# 14_-_MCU.net
KiCad netlist of a schematic drawn in Altium Designer
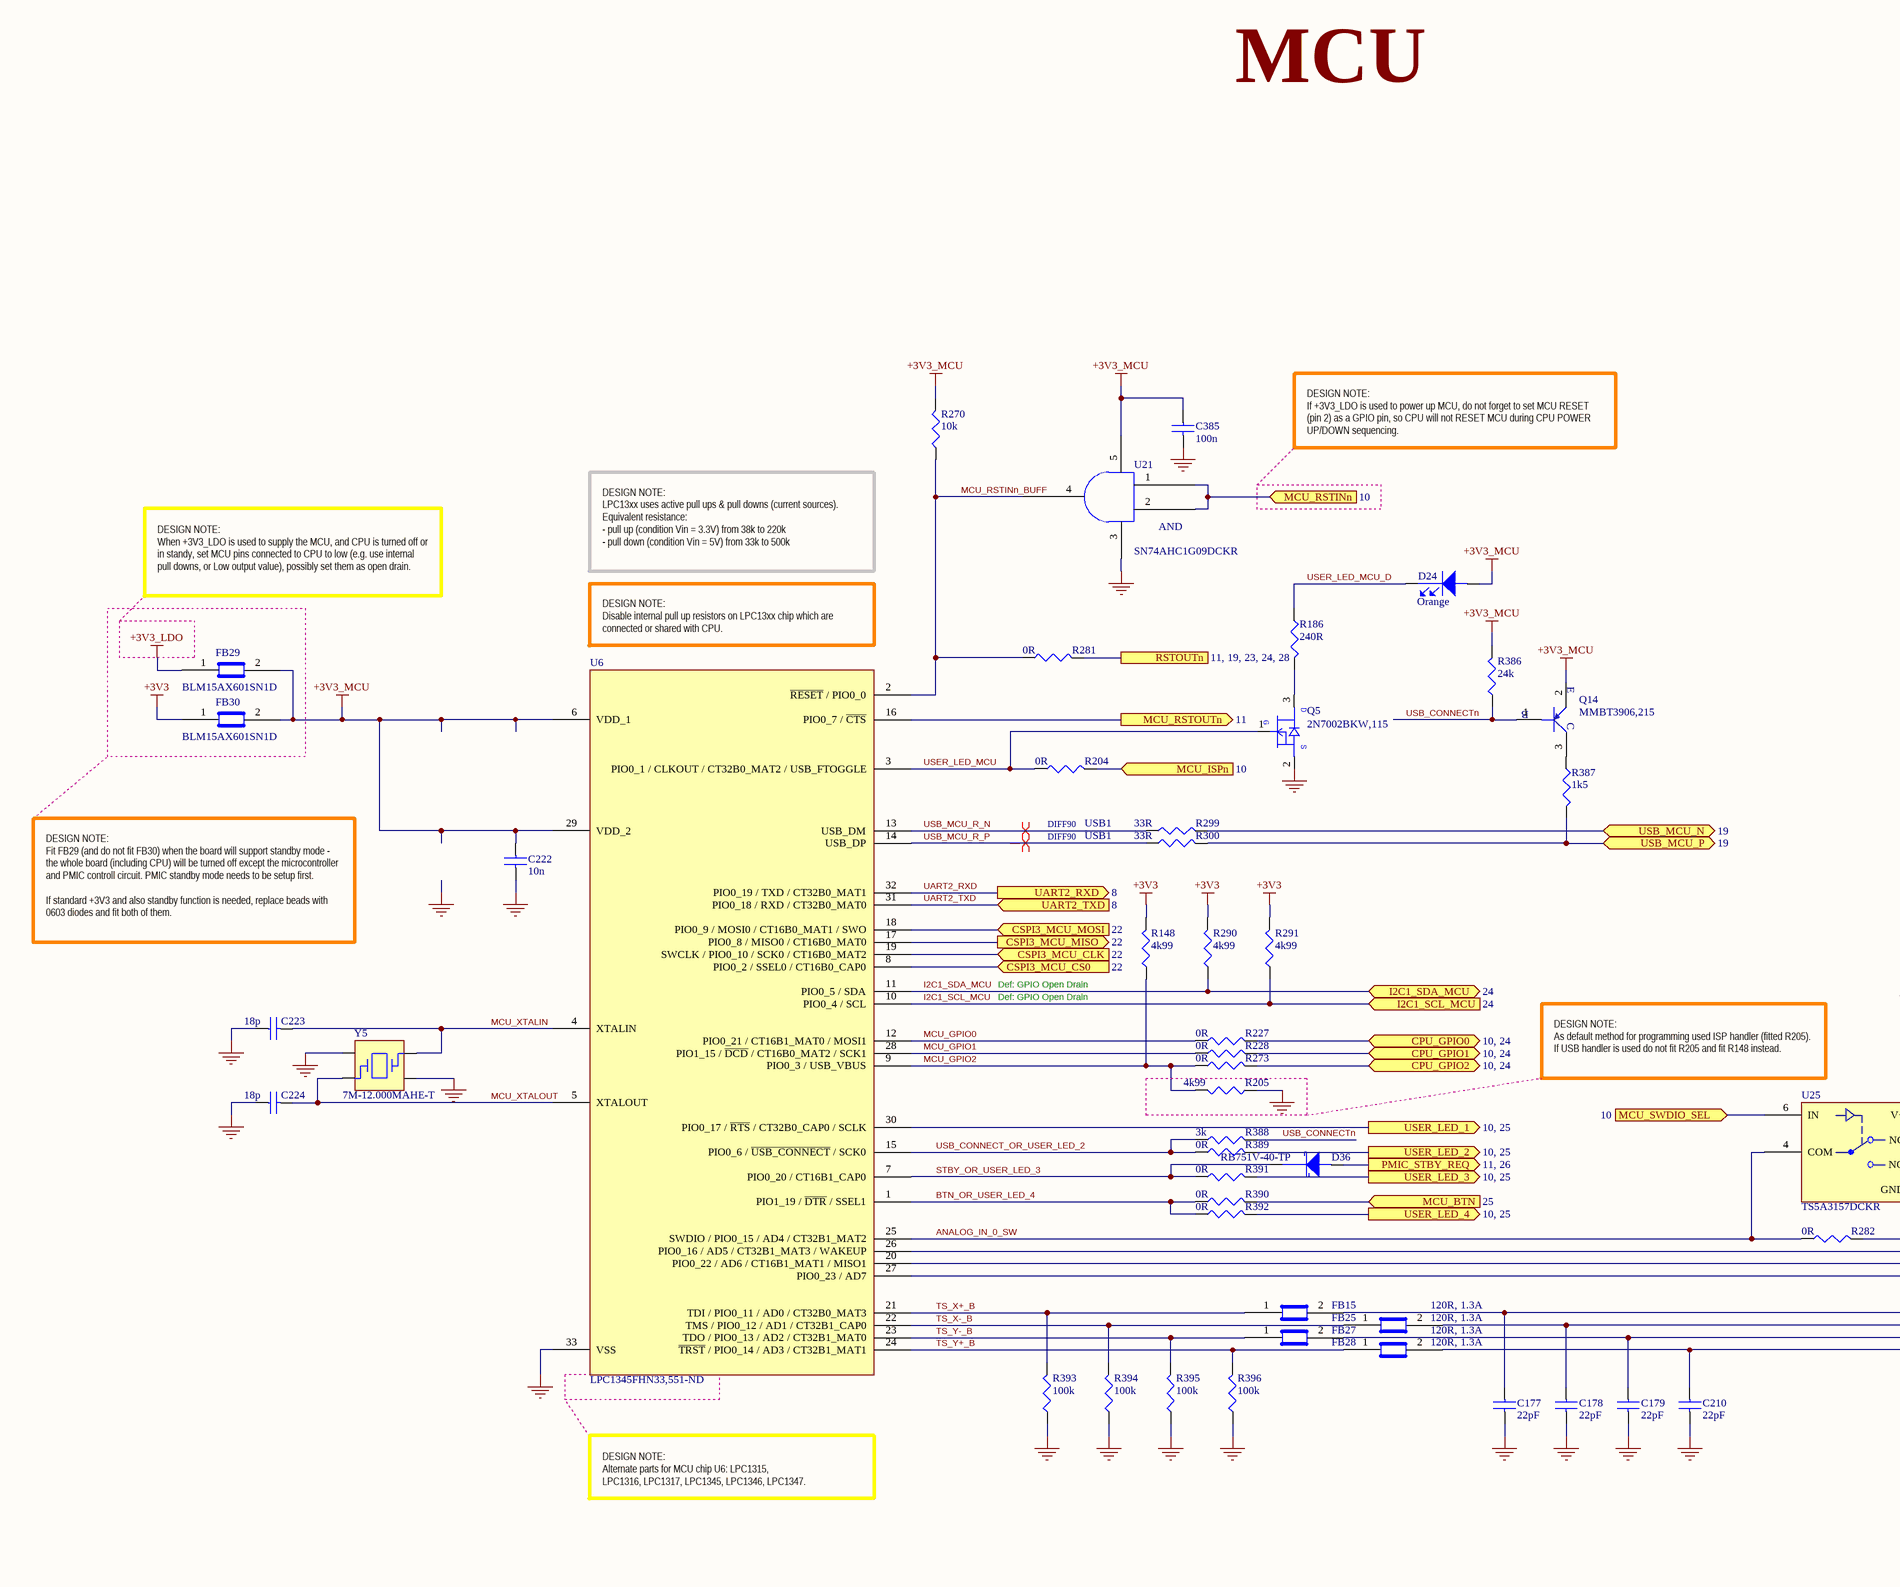
[diagram p0: [14] - MCU.SchDoc, left]
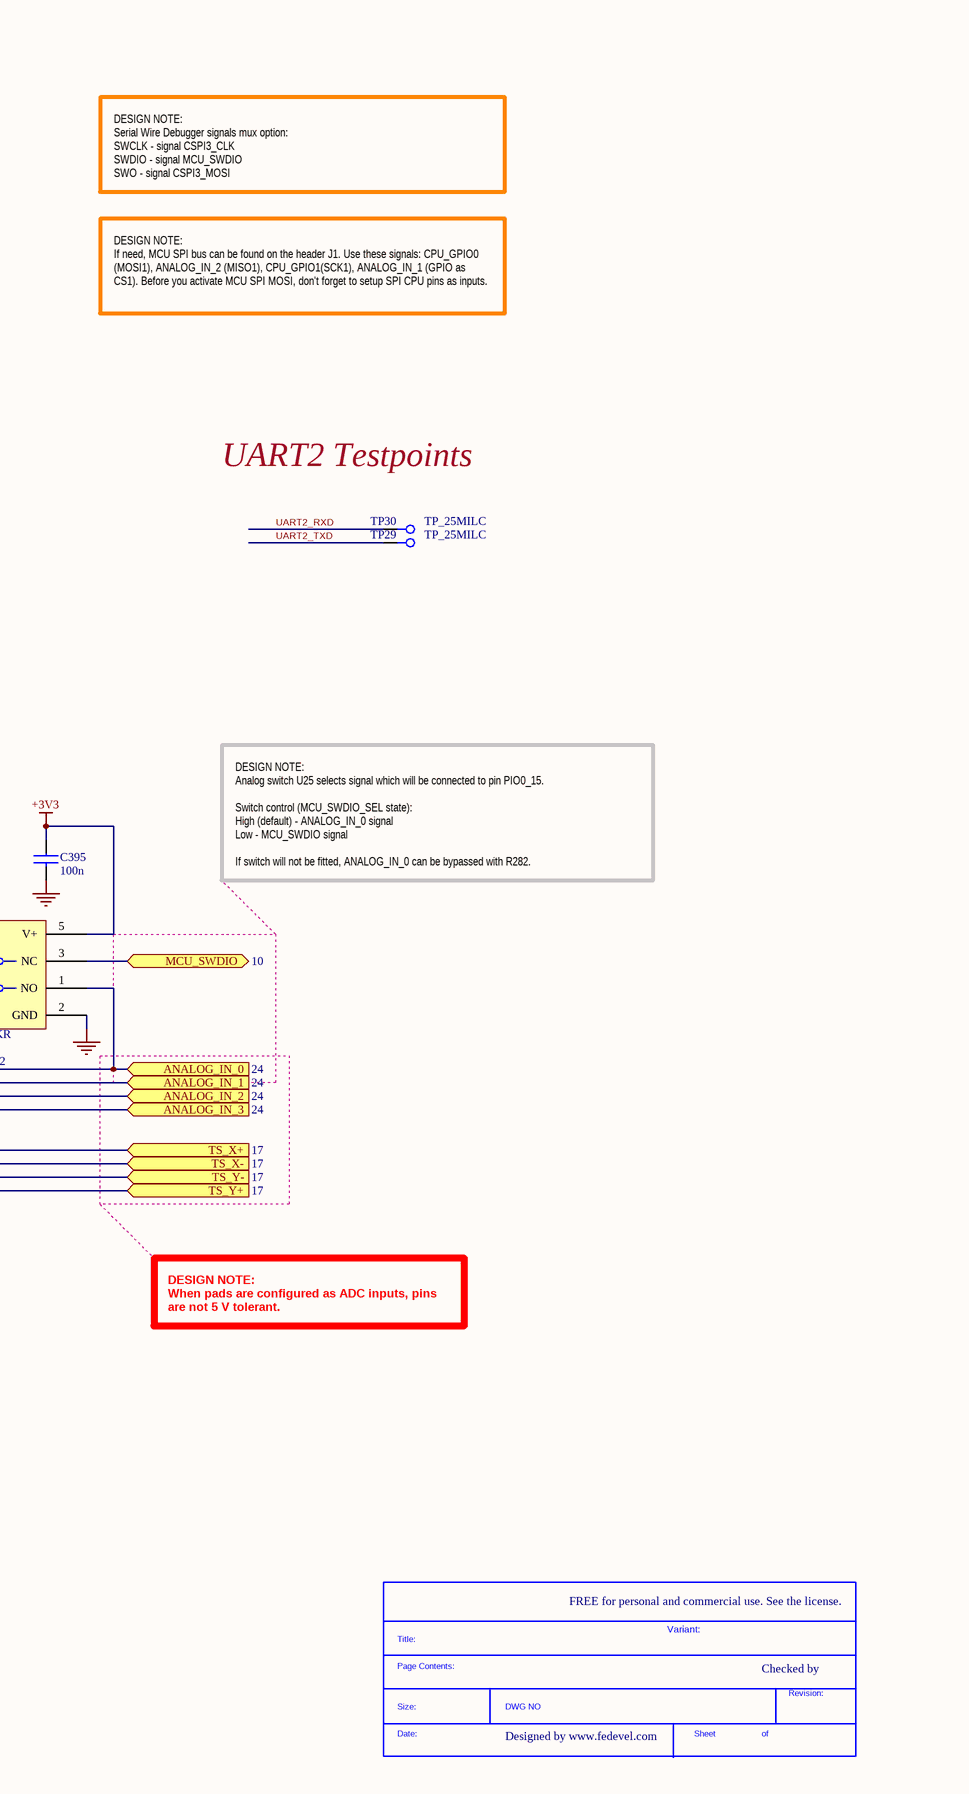
[diagram p1: [14] - MCU.SchDoc, right]

(export (version "E")
  (design (tool "Eeschema 10.0.6"))
  (components
    (comp (ref "C177")
      (value "22pF")
      (footprint "C0402")
      (description "CAP CER 22PF 50V C0G 5% 0402")
      (fields
        (field (name "MANUFACTURER") "TDK Corporation")
        (field (name "MANUFACTURER PART NUMBER") "C1005C0G1H220J")
      )
      (libsource (lib "Integrated_Library_FEDEVEL_APR_2015") (part "C1005C0G1H220J"))
    )
    (comp (ref "C178")
      (value "22pF")
      (footprint "C0402")
      (description "CAP CER 22PF 50V C0G 5% 0402")
      (fields
        (field (name "MANUFACTURER") "TDK Corporation")
        (field (name "MANUFACTURER PART NUMBER") "C1005C0G1H220J")
      )
      (libsource (lib "Integrated_Library_FEDEVEL_APR_2015") (part "C1005C0G1H220J"))
    )
    (comp (ref "C179")
      (value "22pF")
      (footprint "C0402")
      (description "CAP CER 22PF 50V C0G 5% 0402")
      (fields
        (field (name "MANUFACTURER") "TDK Corporation")
        (field (name "MANUFACTURER PART NUMBER") "C1005C0G1H220J")
      )
      (libsource (lib "Integrated_Library_FEDEVEL_APR_2015") (part "C1005C0G1H220J"))
    )
    (comp (ref "C210")
      (value "22pF")
      (footprint "C0402")
      (description "CAP CER 22PF 50V C0G 5% 0402")
      (fields
        (field (name "MANUFACTURER") "TDK Corporation")
        (field (name "MANUFACTURER PART NUMBER") "C1005C0G1H220J")
      )
      (libsource (lib "Integrated_Library_FEDEVEL_APR_2015") (part "C1005C0G1H220J"))
    )
    (comp (ref "C222")
      (value "10n")
      (footprint "C0402")
      (description "CAP CER 10000PF 50V 10% X7R 0402")
      (fields
        (field (name "MANUFACTURER") "TDK Corporation")
        (field (name "MANUFACTURER PART NUMBER") "C1005X7R1H103K")
      )
      (libsource (lib "Integrated_Library_FEDEVEL_APR_2015") (part "C1005X7R1H103K"))
    )
    (comp (ref "C223")
      (value "18p")
      (footprint "C0402")
      (description "CAP CER 18PF 50V C0G 5% 0402")
      (fields
        (field (name "MANUFACTURER") "TDK Corporation")
        (field (name "MANUFACTURER PART NUMBER") "C1005C0G1H180J")
      )
      (libsource (lib "Integrated_Library_FEDEVEL_APR_2015") (part "C1005C0G1H180J"))
    )
    (comp (ref "C224")
      (value "18p")
      (footprint "C0402")
      (description "CAP CER 18PF 50V C0G 5% 0402")
      (fields
        (field (name "MANUFACTURER") "TDK Corporation")
        (field (name "MANUFACTURER PART NUMBER") "C1005C0G1H180J")
      )
      (libsource (lib "Integrated_Library_FEDEVEL_APR_2015") (part "C1005C0G1H180J"))
    )
    (comp (ref "C385")
      (value "100n")
      (footprint "C0402")
      (description "CAP CER .10UF 50V X5R 10% 0402")
      (fields
        (field (name "MANUFACTURER") "TDK Corporation")
        (field (name "MANUFACTURER PART NUMBER") "C1005X5R1H104K")
      )
      (libsource (lib "Integrated_Library_FEDEVEL_APR_2015") (part "C1005X5R1H104K"))
    )
    (comp (ref "C395")
      (value "100n")
      (footprint "C0402")
      (description "CAP CER .10UF 50V X5R 10% 0402")
      (fields
        (field (name "MANUFACTURER") "TDK Corporation")
        (field (name "MANUFACTURER PART NUMBER") "C1005X5R1H104K")
      )
      (libsource (lib "Integrated_Library_FEDEVEL_APR_2015") (part "C1005X5R1H104K"))
    )
    (comp (ref "D24")
      (value "Orange")
      (footprint "LED_0603")
      (description "LED SMARTLED ORANGE 606NM 0603")
      (fields
        (field (name "MANUFACTURER") "OSRAM Opto Semiconductors Inc")
        (field (name "MANUFACTURER PART NUMBER") "LO L29K-H2K1-24-Z")
      )
      (libsource (lib "Integrated_Library_FEDEVEL_APR_2015") (part "LO L29K-H2K1-24-Z"))
    )
    (comp (ref "D36")
      (value "RB751V-40-TP")
      (footprint "SOD323")
      (description "DIODE SCHTKY 30MA 30V SOD-323")
      (fields (field (name "MANUFACTURER") "Micro Commercial Co"))
      (libsource (lib "Integrated_Library_FEDEVEL_APR_2015") (part "RB751V-40-TP"))
    )
    (comp (ref "FB15")
      (value "120R, 1.3A")
      (footprint "C0402")
      (description "FERRITE CHIP 120 OHM 1300MA 0402")
      (fields
        (field (name "MANUFACTURER") "Murata Electronics North America")
        (field (name "MANUFACTURER PART NUMBER") "BLM15PD121SN1D")
        (field (name ".CHECKED PCB") "MM")
        (field (name ".CHECKED SCH") "MM")
        (field (name ".CREATOR") "MM")
      )
      (libsource (lib "Integrated_Library_FEDEVEL_APR_2015") (part "BLM15PD121SN1D"))
    )
    (comp (ref "FB25")
      (value "120R, 1.3A")
      (footprint "C0402")
      (description "FERRITE CHIP 120 OHM 1300MA 0402")
      (fields
        (field (name "MANUFACTURER") "Murata Electronics North America")
        (field (name "MANUFACTURER PART NUMBER") "BLM15PD121SN1D")
        (field (name ".CHECKED PCB") "MM")
        (field (name ".CHECKED SCH") "MM")
        (field (name ".CREATOR") "MM")
      )
      (libsource (lib "Integrated_Library_FEDEVEL_APR_2015") (part "BLM15PD121SN1D"))
    )
    (comp (ref "FB27")
      (value "120R, 1.3A")
      (footprint "C0402")
      (description "FERRITE CHIP 120 OHM 1300MA 0402")
      (fields
        (field (name "MANUFACTURER") "Murata Electronics North America")
        (field (name "MANUFACTURER PART NUMBER") "BLM15PD121SN1D")
        (field (name ".CHECKED PCB") "MM")
        (field (name ".CHECKED SCH") "MM")
        (field (name ".CREATOR") "MM")
      )
      (libsource (lib "Integrated_Library_FEDEVEL_APR_2015") (part "BLM15PD121SN1D"))
    )
    (comp (ref "FB28")
      (value "120R, 1.3A")
      (footprint "C0402")
      (description "FERRITE CHIP 120 OHM 1300MA 0402")
      (fields
        (field (name "MANUFACTURER") "Murata Electronics North America")
        (field (name "MANUFACTURER PART NUMBER") "BLM15PD121SN1D")
        (field (name ".CHECKED PCB") "MM")
        (field (name ".CHECKED SCH") "MM")
        (field (name ".CREATOR") "MM")
      )
      (libsource (lib "Integrated_Library_FEDEVEL_APR_2015") (part "BLM15PD121SN1D"))
    )
    (comp (ref "FB29")
      (value "BLM15AX601SN1D")
      (footprint "C0402")
      (description "FERRITE CHIP 600 OHM 0402 420mA")
      (fields (field (name "MANUFACTURER") "Murata Electronics North America"))
      (libsource (lib "Integrated_Library_FEDEVEL_APR_2015") (part "BLM15AX601SN1D"))
    )
    (comp (ref "FB30")
      (value "BLM15AX601SN1D")
      (footprint "C0402")
      (description "FERRITE CHIP 600 OHM 0402 420mA")
      (fields (field (name "MANUFACTURER") "Murata Electronics North America"))
      (libsource (lib "Integrated_Library_FEDEVEL_APR_2015") (part "BLM15AX601SN1D"))
    )
    (comp (ref "Q5")
      (value "2N7002BKW,115")
      (footprint "SC70_SOT323")
      (description "MOSFET N-CH 60V 310MA SOT323")
      (fields (field (name "MANUFACTURER") "NXP Semiconductors"))
      (libsource (lib "Integrated_Library_FEDEVEL_APR_2015") (part "2N7002BKW,115"))
    )
    (comp (ref "Q14")
      (value "MMBT3906,215")
      (footprint "SOT-23-3-123")
      (description "TRANS PNP 40V 0.2A SOT23")
      (fields
        (field (name "MANUFACTURER") "NXP Semiconductors")
        (field (name ".CHECKED PCB") "MM")
        (field (name ".CHECKED SCH") "MM")
        (field (name ".CREATOR") "MM")
      )
      (libsource (lib "Integrated_Library_FEDEVEL_APR_2015") (part "MMBT3906,215"))
    )
    (comp (ref "R148")
      (value "4k99")
      (footprint "R0402")
      (description "RES TF 4.99K OHM 1% 1/16W 0402")
      (fields
        (field (name "MANUFACTURER") "Stackpole Electronics Inc")
        (field (name "MANUFACTURER PART NUMBER") "RMCF0402FT4K99")
      )
      (libsource (lib "Integrated_Library_FEDEVEL_APR_2015") (part "RMCF0402FT4K99"))
    )
    (comp (ref "R186")
      (value "240R")
      (footprint "R0402")
      (description "RES TF 240 OHM 1% 0.0625W 0402")
      (fields
        (field (name "MANUFACTURER") "Stackpole Electronics Inc")
        (field (name "MANUFACTURER PART NUMBER") "RMCF0402FT240R")
      )
      (libsource (lib "Integrated_Library_FEDEVEL_APR_2015") (part "RMCF0402FT240R"))
    )
    (comp (ref "R204")
      (value "0R")
      (footprint "R0402")
      (description "RES 0.0 OHM 1/16W 0402 SMD")
      (fields
        (field (name "MANUFACTURER") "Yageo")
        (field (name "MANUFACTURER PART NUMBER") "RC0402JR-070RL")
      )
      (libsource (lib "Integrated_Library_FEDEVEL_APR_2015") (part "RC0402JR-070RL"))
    )
    (comp (ref "R205")
      (value "4k99")
      (footprint "R0402")
      (description "RES TF 4.99K OHM 1% 1/16W 0402")
      (fields
        (field (name "MANUFACTURER") "Stackpole Electronics Inc")
        (field (name "MANUFACTURER PART NUMBER") "RMCF0402FT4K99")
      )
      (libsource (lib "Integrated_Library_FEDEVEL_APR_2015") (part "RMCF0402FT4K99"))
    )
    (comp (ref "R227")
      (value "0R")
      (footprint "R0402")
      (description "RES 0.0 OHM 1/16W 0402 SMD")
      (fields
        (field (name "MANUFACTURER") "Yageo")
        (field (name "MANUFACTURER PART NUMBER") "RC0402JR-070RL")
      )
      (libsource (lib "Integrated_Library_FEDEVEL_APR_2015") (part "RC0402JR-070RL"))
    )
    (comp (ref "R228")
      (value "0R")
      (footprint "R0402")
      (description "RES 0.0 OHM 1/16W 0402 SMD")
      (fields
        (field (name "MANUFACTURER") "Yageo")
        (field (name "MANUFACTURER PART NUMBER") "RC0402JR-070RL")
      )
      (libsource (lib "Integrated_Library_FEDEVEL_APR_2015") (part "RC0402JR-070RL"))
    )
    (comp (ref "R270")
      (value "10k")
      (footprint "R0402")
      (description "RES 10.0K OHM 1/16W 1% 0402 SMD")
      (fields
        (field (name "MANUFACTURER") "Yageo")
        (field (name "MANUFACTURER PART NUMBER") "RC0402FR-0710KL")
      )
      (libsource (lib "Integrated_Library_FEDEVEL_APR_2015") (part "RC0402FR-0710KL"))
    )
    (comp (ref "R273")
      (value "0R")
      (footprint "R0402")
      (description "RES 0.0 OHM 1/16W 0402 SMD")
      (fields
        (field (name "MANUFACTURER") "Yageo")
        (field (name "MANUFACTURER PART NUMBER") "RC0402JR-070RL")
      )
      (libsource (lib "Integrated_Library_FEDEVEL_APR_2015") (part "RC0402JR-070RL"))
    )
    (comp (ref "R281")
      (value "0R")
      (footprint "R0402")
      (description "RES 0.0 OHM 1/16W 0402 SMD")
      (fields
        (field (name "MANUFACTURER") "Yageo")
        (field (name "MANUFACTURER PART NUMBER") "RC0402JR-070RL")
      )
      (libsource (lib "Integrated_Library_FEDEVEL_APR_2015") (part "RC0402JR-070RL"))
    )
    (comp (ref "R282")
      (value "0R")
      (footprint "R0402")
      (description "RES 0.0 OHM 1/16W 0402 SMD")
      (fields
        (field (name "MANUFACTURER") "Yageo")
        (field (name "MANUFACTURER PART NUMBER") "RC0402JR-070RL")
      )
      (libsource (lib "Integrated_Library_FEDEVEL_APR_2015") (part "RC0402JR-070RL"))
    )
    (comp (ref "R290")
      (value "4k99")
      (footprint "R0402")
      (description "RES TF 4.99K OHM 1% 1/16W 0402")
      (fields
        (field (name "MANUFACTURER") "Stackpole Electronics Inc")
        (field (name "MANUFACTURER PART NUMBER") "RMCF0402FT4K99")
      )
      (libsource (lib "Integrated_Library_FEDEVEL_APR_2015") (part "RMCF0402FT4K99"))
    )
    (comp (ref "R291")
      (value "4k99")
      (footprint "R0402")
      (description "RES TF 4.99K OHM 1% 1/16W 0402")
      (fields
        (field (name "MANUFACTURER") "Stackpole Electronics Inc")
        (field (name "MANUFACTURER PART NUMBER") "RMCF0402FT4K99")
      )
      (libsource (lib "Integrated_Library_FEDEVEL_APR_2015") (part "RMCF0402FT4K99"))
    )
    (comp (ref "R299")
      (value "33R")
      (footprint "R0402")
      (description "RES TF 33 OHM 1% 1/16W 0402")
      (fields
        (field (name "MANUFACTURER") "Stackpole Electronics Inc")
        (field (name "MANUFACTURER PART NUMBER") "RMCF0402FT33R0")
      )
      (libsource (lib "Integrated_Library_FEDEVEL_APR_2015") (part "RMCF0402FT33R0"))
    )
    (comp (ref "R300")
      (value "33R")
      (footprint "R0402")
      (description "RES TF 33 OHM 1% 1/16W 0402")
      (fields
        (field (name "MANUFACTURER") "Stackpole Electronics Inc")
        (field (name "MANUFACTURER PART NUMBER") "RMCF0402FT33R0")
      )
      (libsource (lib "Integrated_Library_FEDEVEL_APR_2015") (part "RMCF0402FT33R0"))
    )
    (comp (ref "R386")
      (value "24k")
      (footprint "R0402")
      (description "RES SMD 24K OHM 1% 1/16W 0402")
      (fields
        (field (name "MANUFACTURER") "Yageo")
        (field (name "MANUFACTURER PART NUMBER") "RC0402FR-0724KL")
        (field (name ".CREATOR") "MM")
        (field (name ".CHECKED PCB") "MM")
        (field (name ".CHECKED SCH") "MM")
      )
      (libsource (lib "Integrated_Library_FEDEVEL_APR_2015") (part "RC0402FR-0724KL"))
    )
    (comp (ref "R387")
      (value "1k5")
      (footprint "R0402")
      (description "RES 1.50K OHM 1/16W 1% 0402 SMD")
      (fields
        (field (name "MANUFACTURER") "Yageo")
        (field (name "MANUFACTURER PART NUMBER") "RC0402FR-071K5L")
        (field (name ".CREATOR") "MM")
        (field (name ".CHECKED PCB") "MM")
        (field (name ".CHECKED SCH") "MM")
      )
      (libsource (lib "Integrated_Library_FEDEVEL_APR_2015") (part "RC0402FR-071K5L"))
    )
    (comp (ref "R388")
      (value "3k")
      (footprint "R0402")
      (description "RES 3K OHM 1/16W 1% 0402 SMD")
      (fields
        (field (name "MANUFACTURER") "Yageo")
        (field (name "MANUFACTURER PART NUMBER") "RC0402FR-073KL")
        (field (name ".CREATOR") "MM")
      )
      (libsource (lib "Integrated_Library_FEDEVEL_APR_2015") (part "RC0402FR-073KL"))
    )
    (comp (ref "R389")
      (value "0R")
      (footprint "R0402")
      (description "RES 0.0 OHM 1/16W 0402 SMD")
      (fields
        (field (name "MANUFACTURER") "Yageo")
        (field (name "MANUFACTURER PART NUMBER") "RC0402JR-070RL")
      )
      (libsource (lib "Integrated_Library_FEDEVEL_APR_2015") (part "RC0402JR-070RL"))
    )
    (comp (ref "R390")
      (value "0R")
      (footprint "R0402")
      (description "RES 0.0 OHM 1/16W 0402 SMD")
      (fields
        (field (name "MANUFACTURER") "Yageo")
        (field (name "MANUFACTURER PART NUMBER") "RC0402JR-070RL")
      )
      (libsource (lib "Integrated_Library_FEDEVEL_APR_2015") (part "RC0402JR-070RL"))
    )
    (comp (ref "R391")
      (value "0R")
      (footprint "R0402")
      (description "RES 0.0 OHM 1/16W 0402 SMD")
      (fields
        (field (name "MANUFACTURER") "Yageo")
        (field (name "MANUFACTURER PART NUMBER") "RC0402JR-070RL")
      )
      (libsource (lib "Integrated_Library_FEDEVEL_APR_2015") (part "RC0402JR-070RL"))
    )
    (comp (ref "R392")
      (value "0R")
      (footprint "R0402")
      (description "RES 0.0 OHM 1/16W 0402 SMD")
      (fields
        (field (name "MANUFACTURER") "Yageo")
        (field (name "MANUFACTURER PART NUMBER") "RC0402JR-070RL")
      )
      (libsource (lib "Integrated_Library_FEDEVEL_APR_2015") (part "RC0402JR-070RL"))
    )
    (comp (ref "R393")
      (value "100k")
      (footprint "R0402")
      (description "RES 100K OHM 1/16W 1% 0402 SMD")
      (fields
        (field (name "MANUFACTURER") "Stackpole Electronics Inc")
        (field (name "MANUFACTURER PART NUMBER") "RMCF0402FT100K")
      )
      (libsource (lib "Integrated_Library_FEDEVEL_APR_2015") (part "RMCF0402FT100K"))
    )
    (comp (ref "R394")
      (value "100k")
      (footprint "R0402")
      (description "RES 100K OHM 1/16W 1% 0402 SMD")
      (fields
        (field (name "MANUFACTURER") "Stackpole Electronics Inc")
        (field (name "MANUFACTURER PART NUMBER") "RMCF0402FT100K")
      )
      (libsource (lib "Integrated_Library_FEDEVEL_APR_2015") (part "RMCF0402FT100K"))
    )
    (comp (ref "R395")
      (value "100k")
      (footprint "R0402")
      (description "RES 100K OHM 1/16W 1% 0402 SMD")
      (fields
        (field (name "MANUFACTURER") "Stackpole Electronics Inc")
        (field (name "MANUFACTURER PART NUMBER") "RMCF0402FT100K")
      )
      (libsource (lib "Integrated_Library_FEDEVEL_APR_2015") (part "RMCF0402FT100K"))
    )
    (comp (ref "R396")
      (value "100k")
      (footprint "R0402")
      (description "RES 100K OHM 1/16W 1% 0402 SMD")
      (fields
        (field (name "MANUFACTURER") "Stackpole Electronics Inc")
        (field (name "MANUFACTURER PART NUMBER") "RMCF0402FT100K")
      )
      (libsource (lib "Integrated_Library_FEDEVEL_APR_2015") (part "RMCF0402FT100K"))
    )
    (comp (ref "TP29")
      (value "TP_25MILC")
      (footprint "TP_25C")
      (description "Test Point 25mil")
      (libsource (lib "Integrated_Library_FEDEVEL_APR_2015") (part "TP_25MILC"))
    )
    (comp (ref "TP30")
      (value "TP_25MILC")
      (footprint "TP_25C")
      (description "Test Point 25mil")
      (libsource (lib "Integrated_Library_FEDEVEL_APR_2015") (part "TP_25MILC"))
    )
    (comp (ref "U6")
      (value "LPC1345FHN33,551-ND")
      (footprint "HVQFN33_7x7mm")
      (description "IC MCU ARM 32KB FLASH 32HVQFN")
      (fields
        (field (name "MANUFACTURER") "NXP Semiconductors")
        (field (name "MANUFACTURER PART NUMBER") "LPC1345FHN33,551")
        (field (name ".CHECKED PCB") "MM")
        (field (name ".CHECKED SCH") "MM")
        (field (name ".CREATOR") "MM")
      )
      (libsource (lib "Integrated_Library_FEDEVEL_APR_2015") (part "LPC1345FHN33,551"))
    )
    (comp (ref "U21")
      (value "SN74AHC1G09DCKR")
      (footprint "SC70_5")
      (description "IC GATE AND 1CH 2-INP SC-70-5")
      (fields
        (field (name "MANUFACTURER") "Texas Instruments")
        (field (name ".CREATOR") "MM")
        (field (name ".CHECKED SCH") "MM")
        (field (name ".CHECKED PCB") "RF, used by MM")
      )
      (libsource (lib "Integrated_Library_FEDEVEL_APR_2015") (part "SN74AHC1G09DCKR"))
    )
    (comp (ref "U25")
      (value "TS5A3157DCKR")
      (footprint "SC70_6")
      (description "IC SWITCH SPDT SC70-6")
      (fields
        (field (name "MANUFACTURER") "Texas Instruments")
        (field (name ".CHECKED PCB") "MM")
        (field (name ".CHECKED SCH") "MM")
        (field (name ".CREATOR") "MM")
      )
      (libsource (lib "Integrated_Library_FEDEVEL_APR_2015") (part "TS5A3157DCKR"))
    )
    (comp (ref "Y5")
      (value "7M-12.000MAHE-T")
      (footprint "7M")
      (description "CRYSTAL 12MHZ 12PF SMD")
      (fields
        (field (name "MANUFACTURER") "TXC CORPORATION")
        (field (name ".CREATOR") "MM")
        (field (name ".CHECKED PCB") "MM")
        (field (name ".CHECKED SCH") "MM")
      )
      (libsource (lib "Integrated_Library_FEDEVEL_APR_2015") (part "7M-12.000MAHE-T"))
    )
  )
  (nets
    (net (code "1") (name "+3V3") (class "Default")
      (node (ref "C395") (pin "1") (pinfunction "1_1") (pintype "passive"))
      (node (ref "FB30") (pin "1") (pinfunction "1_1") (pintype "passive"))
      (node (ref "R148") (pin "2") (pinfunction "2_2") (pintype "passive"))
      (node (ref "R290") (pin "2") (pinfunction "2_2") (pintype "passive"))
      (node (ref "R291") (pin "2") (pinfunction "2_2") (pintype "passive"))
      (node (ref "U25") (pin "5") (pinfunction "V+_5") (pintype "passive"))
    )
    (net (code "2") (name "+3V3_LDO") (class "Default")
      (node (ref "FB29") (pin "1") (pinfunction "1_1") (pintype "passive"))
    )
    (net (code "3") (name "+3V3_MCU") (class "Default")
      (node (ref "C222") (pin "1") (pinfunction "1_1") (pintype "passive"))
      (node (ref "C385") (pin "1") (pinfunction "1_1") (pintype "passive"))
      (node (ref "D24") (pin "2") (pinfunction "ANODE_2") (pintype "passive"))
      (node (ref "FB29") (pin "2") (pinfunction "2_2") (pintype "passive"))
      (node (ref "FB30") (pin "2") (pinfunction "2_2") (pintype "passive"))
      (node (ref "Q14") (pin "2") (pinfunction "E_2") (pintype "passive"))
      (node (ref "R270") (pin "2") (pinfunction "2_2") (pintype "passive"))
      (node (ref "R386") (pin "2") (pinfunction "2_2") (pintype "passive"))
      (node (ref "U21") (pin "5") (pinfunction "VCC_5") (pintype "power_in"))
      (node (ref "U6") (pin "29") (pinfunction "VDD_2_29") (pintype "passive"))
      (node (ref "U6") (pin "6") (pinfunction "VDD_1_6") (pintype "passive"))
    )
    (net (code "4") (name "/ANALOG_IN_0") (class "Default")
      (node (ref "R282") (pin "2") (pinfunction "2_2") (pintype "passive"))
      (node (ref "U25") (pin "1") (pinfunction "NO_1") (pintype "passive"))
    )
    (net (code "5") (name "/ANALOG_IN_0_SW") (class "Default")
      (node (ref "R282") (pin "1") (pinfunction "1_1") (pintype "passive"))
      (node (ref "U25") (pin "4") (pinfunction "COM_4") (pintype "passive"))
      (node (ref "U6") (pin "25") (pinfunction "SWDIO_/_PIO0_15_/_AD4_/_CT32B1_MAT2_25") (pintype "passive"))
    )
    (net (code "6") (name "/ANALOG_IN_1") (class "Default")
      (node (ref "U6") (pin "26") (pinfunction "PIO0_16_/_AD5_/_CT32B1_MAT3_/_WAKEUP_26") (pintype "passive"))
    )
    (net (code "7") (name "/ANALOG_IN_2") (class "Default")
      (node (ref "U6") (pin "20") (pinfunction "PIO0_22_/_AD6_/_CT16B1_MAT1_/_MISO1_20") (pintype "passive"))
    )
    (net (code "8") (name "/ANALOG_IN_3") (class "Default")
      (node (ref "U6") (pin "27") (pinfunction "PIO0_23_/_AD7_27") (pintype "passive"))
    )
    (net (code "9") (name "/BTN_OR_USER_LED_4") (class "Default")
      (node (ref "R390") (pin "1") (pinfunction "1_1") (pintype "passive"))
      (node (ref "R392") (pin "1") (pinfunction "1_1") (pintype "passive"))
      (node (ref "U6") (pin "1") (pinfunction "PIO1_19_/_~{DTR}_/_SSEL1_1") (pintype "passive"))
    )
    (net (code "10") (name "/CPU_GPIO0") (class "Default")
      (node (ref "R227") (pin "2") (pinfunction "2_2") (pintype "passive"))
    )
    (net (code "11") (name "/CPU_GPIO1") (class "Default")
      (node (ref "R228") (pin "2") (pinfunction "2_2") (pintype "passive"))
    )
    (net (code "12") (name "/CPU_GPIO2") (class "Default")
      (node (ref "R273") (pin "2") (pinfunction "2_2") (pintype "passive"))
    )
    (net (code "13") (name "/CSPI3_MCU_CLK") (class "Default")
      (node (ref "U6") (pin "19") (pinfunction "SWCLK_/_PIO0_10_/_SCK0_/_CT16B0_MAT2_19") (pintype "passive"))
    )
    (net (code "14") (name "/CSPI3_MCU_CS0") (class "Default")
      (node (ref "U6") (pin "8") (pinfunction "PIO0_2_/_SSEL0_/_CT16B0_CAP0_8") (pintype "passive"))
    )
    (net (code "15") (name "/CSPI3_MCU_MISO") (class "Default")
      (node (ref "U6") (pin "17") (pinfunction "PIO0_8_/_MISO0_/_CT16B0_MAT0_17") (pintype "passive"))
    )
    (net (code "16") (name "/CSPI3_MCU_MOSI") (class "Default")
      (node (ref "U6") (pin "18") (pinfunction "PIO0_9_/_MOSI0_/_CT16B0_MAT1_/_SWO_18") (pintype "passive"))
    )
    (net (code "17") (name "/I2C1_SCL_MCU") (class "Default")
      (node (ref "R291") (pin "1") (pinfunction "1_1") (pintype "passive"))
      (node (ref "U6") (pin "10") (pinfunction "PIO0_4_/_SCL_10") (pintype "passive"))
    )
    (net (code "18") (name "/I2C1_SDA_MCU") (class "Default")
      (node (ref "R290") (pin "1") (pinfunction "1_1") (pintype "passive"))
      (node (ref "U6") (pin "11") (pinfunction "PIO0_5_/_SDA_11") (pintype "passive"))
    )
    (net (code "19") (name "/MCU_BTN") (class "Default")
      (node (ref "R390") (pin "2") (pinfunction "2_2") (pintype "passive"))
    )
    (net (code "20") (name "/MCU_GPIO0") (class "Default")
      (node (ref "R227") (pin "1") (pinfunction "1_1") (pintype "passive"))
      (node (ref "U6") (pin "12") (pinfunction "PIO0_21_/_CT16B1_MAT0_/_MOSI1_12") (pintype "passive"))
    )
    (net (code "21") (name "/MCU_GPIO1") (class "Default")
      (node (ref "R228") (pin "1") (pinfunction "1_1") (pintype "passive"))
      (node (ref "U6") (pin "28") (pinfunction "PIO1_15_/_~{DCD}_/_CT16B0_MAT2_/_SCK1_28") (pintype "passive"))
    )
    (net (code "22") (name "/MCU_GPIO2") (class "Default")
      (node (ref "R148") (pin "1") (pinfunction "1_1") (pintype "passive"))
      (node (ref "R205") (pin "2") (pinfunction "2_2") (pintype "passive"))
      (node (ref "R273") (pin "1") (pinfunction "1_1") (pintype "passive"))
      (node (ref "U6") (pin "9") (pinfunction "PIO0_3_/_USB_VBUS_9") (pintype "passive"))
    )
    (net (code "23") (name "/MCU_ISPn") (class "Default")
      (node (ref "R204") (pin "2") (pinfunction "2_2") (pintype "passive"))
    )
    (net (code "24") (name "/MCU_RSTINn") (class "Default")
      (node (ref "U21") (pin "1") (pinfunction "A_1") (pintype "passive"))
      (node (ref "U21") (pin "2") (pinfunction "B_2") (pintype "passive"))
    )
    (net (code "25") (name "/MCU_RSTINn_BUFF") (class "Default")
      (node (ref "R270") (pin "1") (pinfunction "1_1") (pintype "passive"))
      (node (ref "R281") (pin "1") (pinfunction "1_1") (pintype "passive"))
      (node (ref "U21") (pin "4") (pinfunction "Y_4") (pintype "passive"))
      (node (ref "U6") (pin "2") (pinfunction "~{RESET}_/_PIO0_0_2") (pintype "passive"))
    )
    (net (code "26") (name "/MCU_RSTOUTn") (class "Default")
      (node (ref "U6") (pin "16") (pinfunction "PIO0_7_/_~{CTS}_16") (pintype "passive"))
    )
    (net (code "27") (name "/MCU_SWDIO") (class "Default")
      (node (ref "U25") (pin "3") (pinfunction "NC_3") (pintype "passive"))
    )
    (net (code "28") (name "/MCU_SWDIO_SEL") (class "Default")
      (node (ref "U25") (pin "6") (pinfunction "IN_6") (pintype "passive"))
    )
    (net (code "29") (name "/MCU_XTALIN") (class "Default")
      (node (ref "C223") (pin "2") (pinfunction "2_2") (pintype "passive"))
      (node (ref "U6") (pin "4") (pinfunction "XTALIN_4") (pintype "passive"))
      (node (ref "Y5") (pin "1") (pinfunction "1_1") (pintype "passive"))
    )
    (net (code "30") (name "/MCU_XTALOUT") (class "Default")
      (node (ref "C224") (pin "2") (pinfunction "2_2") (pintype "passive"))
      (node (ref "U6") (pin "5") (pinfunction "XTALOUT_5") (pintype "passive"))
      (node (ref "Y5") (pin "3") (pinfunction "3_3") (pintype "passive"))
    )
    (net (code "31") (name "/PMIC_STBY_REQ") (class "Default")
      (node (ref "D36") (pin "2") (pinfunction "ANODE_2") (pintype "passive"))
    )
    (net (code "32") (name "/RSTOUTn") (class "Default")
      (node (ref "R281") (pin "2") (pinfunction "2_2") (pintype "passive"))
    )
    (net (code "33") (name "/STBY_OR_USER_LED_3") (class "Default")
      (node (ref "D36") (pin "1") (pinfunction "cathode_1") (pintype "passive"))
      (node (ref "R391") (pin "1") (pinfunction "1_1") (pintype "passive"))
      (node (ref "U6") (pin "7") (pinfunction "PIO0_20_/_CT16B1_CAP0_7") (pintype "passive"))
    )
    (net (code "34") (name "/TS_X+") (class "Default")
      (node (ref "C177") (pin "1") (pinfunction "1_1") (pintype "passive"))
      (node (ref "FB15") (pin "2") (pinfunction "2_2") (pintype "passive"))
    )
    (net (code "35") (name "/TS_X+_B") (class "Default")
      (node (ref "FB15") (pin "1") (pinfunction "1_1") (pintype "passive"))
      (node (ref "R393") (pin "2") (pinfunction "2_2") (pintype "passive"))
      (node (ref "U6") (pin "21") (pinfunction "TDI_/_PIO0_11_/_AD0_/_CT32B0_MAT3_21") (pintype "passive"))
    )
    (net (code "36") (name "/TS_X-") (class "Default")
      (node (ref "C178") (pin "1") (pinfunction "1_1") (pintype "passive"))
      (node (ref "FB25") (pin "2") (pinfunction "2_2") (pintype "passive"))
    )
    (net (code "37") (name "/TS_X-_B") (class "Default")
      (node (ref "FB25") (pin "1") (pinfunction "1_1") (pintype "passive"))
      (node (ref "R394") (pin "2") (pinfunction "2_2") (pintype "passive"))
      (node (ref "U6") (pin "22") (pinfunction "TMS_/_PIO0_12_/_AD1_/_CT32B1_CAP0_22") (pintype "passive"))
    )
    (net (code "38") (name "/TS_Y+") (class "Default")
      (node (ref "C210") (pin "1") (pinfunction "1_1") (pintype "passive"))
      (node (ref "FB28") (pin "2") (pinfunction "2_2") (pintype "passive"))
    )
    (net (code "39") (name "/TS_Y+_B") (class "Default")
      (node (ref "FB28") (pin "1") (pinfunction "1_1") (pintype "passive"))
      (node (ref "R396") (pin "2") (pinfunction "2_2") (pintype "passive"))
      (node (ref "U6") (pin "24") (pinfunction "~{TRST}_/_PIO0_14_/_AD3_/_CT32B1_MAT1_24") (pintype "passive"))
    )
    (net (code "40") (name "/TS_Y-") (class "Default")
      (node (ref "C179") (pin "1") (pinfunction "1_1") (pintype "passive"))
      (node (ref "FB27") (pin "2") (pinfunction "2_2") (pintype "passive"))
    )
    (net (code "41") (name "/TS_Y-_B") (class "Default")
      (node (ref "FB27") (pin "1") (pinfunction "1_1") (pintype "passive"))
      (node (ref "R395") (pin "2") (pinfunction "2_2") (pintype "passive"))
      (node (ref "U6") (pin "23") (pinfunction "TDO_/_PIO0_13_/_AD2_/_CT32B1_MAT0_23") (pintype "passive"))
    )
    (net (code "42") (name "/UART2_RXD") (class "Default")
      (node (ref "TP30") (pin "1") (pinfunction "1_1") (pintype "passive"))
      (node (ref "U6") (pin "32") (pinfunction "PIO0_19_/_TXD_/_CT32B0_MAT1_32") (pintype "passive"))
    )
    (net (code "43") (name "/UART2_TXD") (class "Default")
      (node (ref "TP29") (pin "1") (pinfunction "1_1") (pintype "passive"))
      (node (ref "U6") (pin "31") (pinfunction "PIO0_18_/_RXD_/_CT32B0_MAT0_31") (pintype "passive"))
    )
    (net (code "44") (name "/USB_CONNECT_OR_USER_LED_2") (class "Default")
      (node (ref "R388") (pin "1") (pinfunction "1_1") (pintype "passive"))
      (node (ref "R389") (pin "1") (pinfunction "1_1") (pintype "passive"))
      (node (ref "U6") (pin "15") (pinfunction "PIO0_6_/_~{USB_CONNECT}_/_SCK0_15") (pintype "passive"))
    )
    (net (code "45") (name "/USB_CONNECTn") (class "Default")
      (node (ref "Q14") (pin "1") (pinfunction "B_1") (pintype "passive"))
      (node (ref "R386") (pin "1") (pinfunction "1_1") (pintype "passive"))
      (node (ref "R388") (pin "2") (pinfunction "2_2") (pintype "passive"))
    )
    (net (code "46") (name "/USB_MCU_N") (class "Default")
      (node (ref "R299") (pin "2") (pinfunction "2_2") (pintype "passive"))
    )
    (net (code "47") (name "/USB_MCU_P") (class "Default")
      (node (ref "R300") (pin "2") (pinfunction "2_2") (pintype "passive"))
      (node (ref "R387") (pin "2") (pinfunction "2_2") (pintype "passive"))
    )
    (net (code "48") (name "/USB_MCU_R_N") (class "Default")
      (node (ref "R299") (pin "1") (pinfunction "1_1") (pintype "passive"))
      (node (ref "U6") (pin "13") (pinfunction "USB_DM_13") (pintype "passive"))
    )
    (net (code "49") (name "/USB_MCU_R_P") (class "Default")
      (node (ref "R300") (pin "1") (pinfunction "1_1") (pintype "passive"))
      (node (ref "U6") (pin "14") (pinfunction "USB_DP_14") (pintype "passive"))
    )
    (net (code "50") (name "/USER_LED_1") (class "Default")
      (node (ref "U6") (pin "30") (pinfunction "PIO0_17_/_~{RTS}_/_CT32B0_CAP0_/_SCLK_30") (pintype "passive"))
    )
    (net (code "51") (name "/USER_LED_2") (class "Default")
      (node (ref "R389") (pin "2") (pinfunction "2_2") (pintype "passive"))
    )
    (net (code "52") (name "/USER_LED_3") (class "Default")
      (node (ref "R391") (pin "2") (pinfunction "2_2") (pintype "passive"))
    )
    (net (code "53") (name "/USER_LED_4") (class "Default")
      (node (ref "R392") (pin "2") (pinfunction "2_2") (pintype "passive"))
    )
    (net (code "54") (name "/USER_LED_MCU") (class "Default")
      (node (ref "Q5") (pin "1") (pinfunction "GATE_1") (pintype "passive"))
      (node (ref "R204") (pin "1") (pinfunction "1_1") (pintype "passive"))
      (node (ref "U6") (pin "3") (pinfunction "PIO0_1_/_CLKOUT_/_CT32B0_MAT2_/_USB_FTOGGLE_3") (pintype "passive"))
    )
    (net (code "55") (name "/USER_LED_MCU_D") (class "Default")
      (node (ref "D24") (pin "1") (pinfunction "cathode_1") (pintype "passive"))
      (node (ref "R186") (pin "1") (pinfunction "1_1") (pintype "passive"))
    )
    (net (code "56") (name "GND") (class "Default")
      (node (ref "C177") (pin "2") (pinfunction "2_2") (pintype "passive"))
      (node (ref "C178") (pin "2") (pinfunction "2_2") (pintype "passive"))
      (node (ref "C179") (pin "2") (pinfunction "2_2") (pintype "passive"))
      (node (ref "C210") (pin "2") (pinfunction "2_2") (pintype "passive"))
      (node (ref "C222") (pin "2") (pinfunction "2_2") (pintype "passive"))
      (node (ref "C223") (pin "1") (pinfunction "1_1") (pintype "passive"))
      (node (ref "C224") (pin "1") (pinfunction "1_1") (pintype "passive"))
      (node (ref "C385") (pin "2") (pinfunction "2_2") (pintype "passive"))
      (node (ref "C395") (pin "2") (pinfunction "2_2") (pintype "passive"))
      (node (ref "Q5") (pin "2") (pinfunction "SOURCE_2") (pintype "passive"))
      (node (ref "R205") (pin "1") (pinfunction "1_1") (pintype "passive"))
      (node (ref "R393") (pin "1") (pinfunction "1_1") (pintype "passive"))
      (node (ref "R394") (pin "1") (pinfunction "1_1") (pintype "passive"))
      (node (ref "R395") (pin "1") (pinfunction "1_1") (pintype "passive"))
      (node (ref "R396") (pin "1") (pinfunction "1_1") (pintype "passive"))
      (node (ref "U21") (pin "3") (pinfunction "GND_3") (pintype "power_in"))
      (node (ref "U25") (pin "2") (pinfunction "GND_2") (pintype "passive"))
      (node (ref "U6") (pin "33") (pinfunction "VSS_33") (pintype "passive"))
      (node (ref "Y5") (pin "2") (pinfunction "2_2") (pintype "passive"))
      (node (ref "Y5") (pin "4") (pinfunction "4_4") (pintype "passive"))
    )
    (net (code "57") (name "Net-(Q5-DRAIN)") (class "Default")
      (node (ref "Q5") (pin "3") (pinfunction "DRAIN_3") (pintype "passive"))
      (node (ref "R186") (pin "2") (pinfunction "2_2") (pintype "passive"))
    )
    (net (code "58") (name "Net-(Q14-C)") (class "Default")
      (node (ref "Q14") (pin "3") (pinfunction "C_3") (pintype "passive"))
      (node (ref "R387") (pin "1") (pinfunction "1_1") (pintype "passive"))
    )
  )
)
